# MCU.net
KiCad netlist of a schematic drawn in Altium Designer
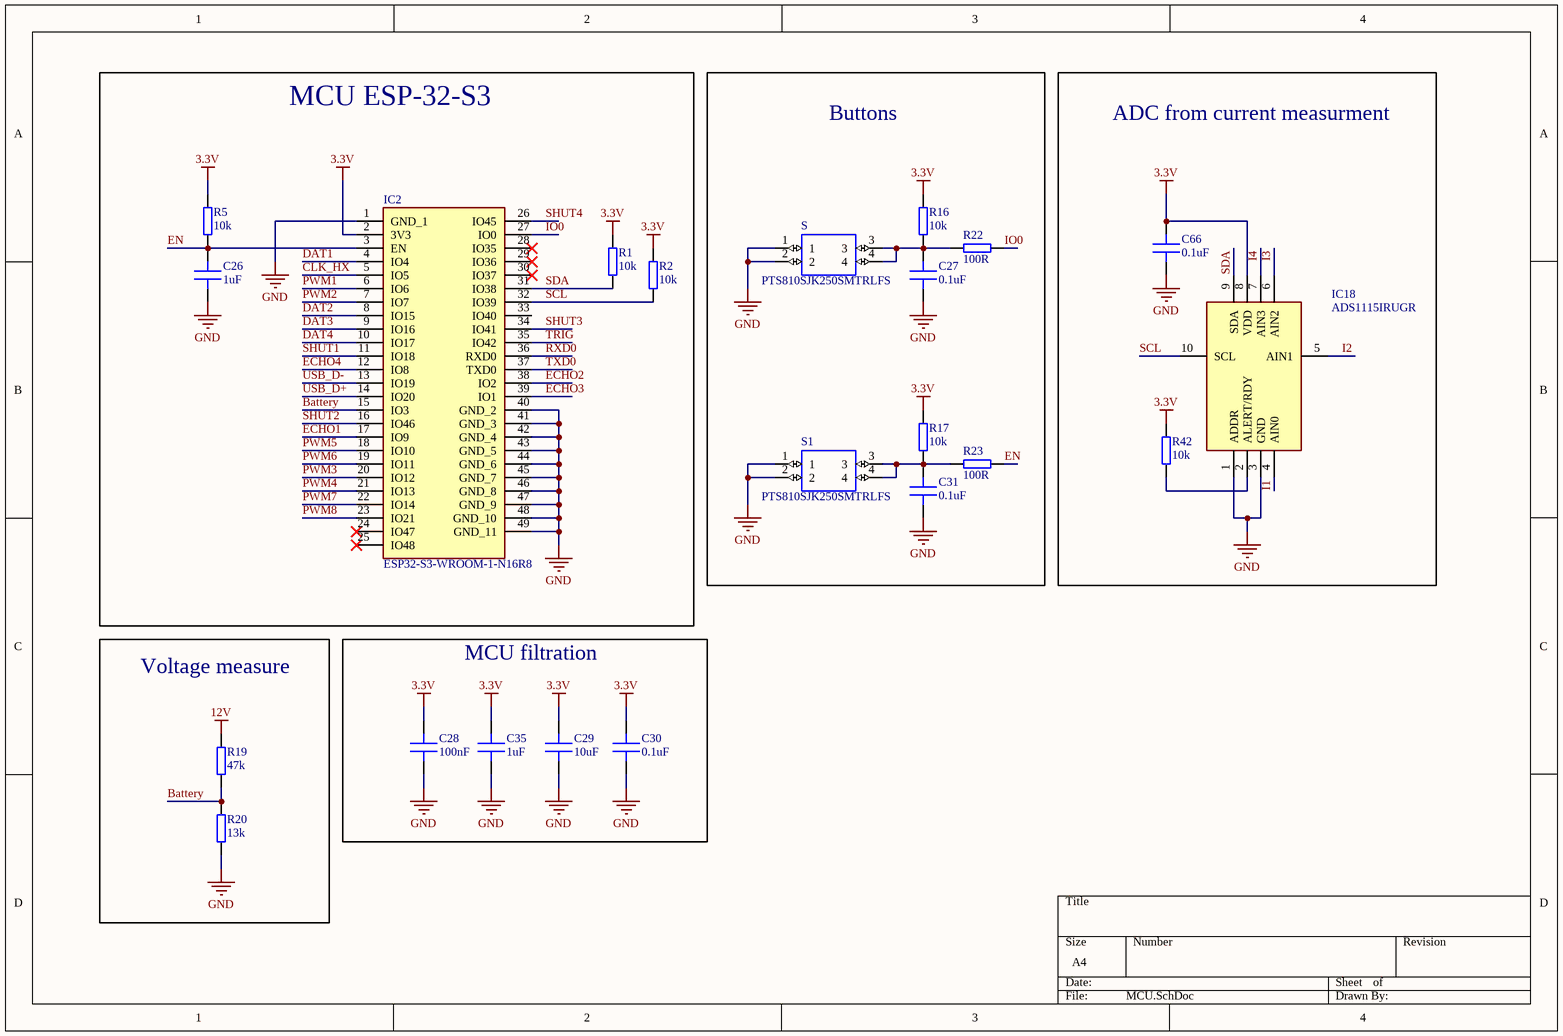
[diagram p0: MCU.SchDoc]

(export (version "E")
  (design (tool "Eeschema 10.0.6"))
  (components
    (comp (ref "C26")
      (value "1uF")
      (footprint "C 0402")
      (description "MLCC Capacitor")
      (libsource (lib "Components") (part "Capacitor"))
    )
    (comp (ref "C27")
      (value "0.1uF")
      (footprint "C 0402")
      (description "MLCC Capacitor")
      (libsource (lib "Components") (part "Capacitor"))
    )
    (comp (ref "C28")
      (value "100nF")
      (footprint "C 0402")
      (description "MLCC Capacitor")
      (libsource (lib "Components") (part "Capacitor"))
    )
    (comp (ref "C29")
      (value "10uF")
      (footprint "C 0402")
      (description "MLCC Capacitor")
      (libsource (lib "Components") (part "Capacitor"))
    )
    (comp (ref "C30")
      (value "0.1uF")
      (footprint "C 0402")
      (description "MLCC Capacitor")
      (libsource (lib "Components") (part "Capacitor"))
    )
    (comp (ref "C31")
      (value "0.1uF")
      (footprint "C 0402")
      (description "MLCC Capacitor")
      (libsource (lib "Components") (part "Capacitor"))
    )
    (comp (ref "C35")
      (value "1uF")
      (footprint "C 0402")
      (description "MLCC Capacitor")
      (libsource (lib "Components") (part "Capacitor"))
    )
    (comp (ref "C66")
      (value "0.1uF")
      (footprint "C 0402")
      (description "MLCC Capacitor")
      (libsource (lib "Components") (part "Capacitor"))
    )
    (comp (ref "IC2")
      (value "ESP32-S3-WROOM-1-N16R8")
      (footprint "SamacSys:ESP32S3WROOM1N16R8")
      (description "Integrated Circuit")
      (fields (field (name "MOUSER PART NUMBER") "356-ESP32S3WRM1N16R8"))
      (libsource (lib "caravan_sch_lib") (part "ESP32-S3-WROOM-1-N16R8"))
    )
    (comp (ref "IC18")
      (value "ADS1115IRUGR")
      (footprint "SamacSys:ADS1115IRUGR")
      (description "Integrated Circuit")
      (fields (field (name "MOUSER PART NUMBER") "595-ADS1115IRUGR"))
      (libsource (lib "caravan_sch_lib") (part "ADS1115IRUGR"))
    )
    (comp (ref "R1")
      (value "10k")
      (footprint "R 0402")
      (description "General pourpouse resistor")
      (libsource (lib "Components") (part "Resistor"))
    )
    (comp (ref "R2")
      (value "10k")
      (footprint "R 0402")
      (description "General pourpouse resistor")
      (libsource (lib "Components") (part "Resistor"))
    )
    (comp (ref "R5")
      (value "10k")
      (footprint "R 0402")
      (description "General pourpouse resistor")
      (libsource (lib "Components") (part "Resistor"))
    )
    (comp (ref "R16")
      (value "10k")
      (footprint "R 0402")
      (description "General pourpouse resistor")
      (libsource (lib "Components") (part "Resistor"))
    )
    (comp (ref "R17")
      (value "10k")
      (footprint "R 0402")
      (description "General pourpouse resistor")
      (libsource (lib "Components") (part "Resistor"))
    )
    (comp (ref "R19")
      (value "47k")
      (footprint "R 0402")
      (description "General pourpouse resistor")
      (libsource (lib "Components") (part "Resistor"))
    )
    (comp (ref "R20")
      (value "13k")
      (footprint "R 0402")
      (description "General pourpouse resistor")
      (libsource (lib "Components") (part "Resistor"))
    )
    (comp (ref "R22")
      (value "100R")
      (footprint "R 0402")
      (description "General pourpouse resistor")
      (libsource (lib "Components") (part "Resistor"))
    )
    (comp (ref "R23")
      (value "100R")
      (footprint "R 0402")
      (description "General pourpouse resistor")
      (libsource (lib "Components") (part "Resistor"))
    )
    (comp (ref "R42")
      (value "10k")
      (footprint "R 0402")
      (description "General pourpouse resistor")
      (libsource (lib "Components") (part "Resistor"))
    )
    (comp (ref "S")
      (value "PTS810SJK250SMTRLFS")
      (footprint "caravan_pcb_lib:PTS810SJG250SMTRLFS")
      (description "Tactile Switch SPST-NO Top Actuated Surface Mount")
      (fields (field (name "MF") "C&K"))
      (libsource (lib "caravan_sch_lib") (part "PTS810SJK250SMTRLFS"))
    )
    (comp (ref "S1")
      (value "PTS810SJK250SMTRLFS")
      (footprint "caravan_pcb_lib:PTS810SJG250SMTRLFS")
      (description "Tactile Switch SPST-NO Top Actuated Surface Mount")
      (fields (field (name "MF") "C&K"))
      (libsource (lib "caravan_sch_lib") (part "PTS810SJK250SMTRLFS"))
    )
  )
  (nets
    (net (code "1") (name "/Battery") (class "Default")
      (node (ref "IC2") (pin "15") (pinfunction "IO3_15") (pintype "passive"))
      (node (ref "R19") (pin "1") (pinfunction "1_1") (pintype "passive"))
      (node (ref "R20") (pin "2") (pinfunction "2_2") (pintype "passive"))
    )
    (net (code "2") (name "/CLK_HX") (class "Default")
      (node (ref "IC2") (pin "5") (pinfunction "IO5_5") (pintype "passive"))
    )
    (net (code "3") (name "/DAT1") (class "Default")
      (node (ref "IC2") (pin "4") (pinfunction "IO4_4") (pintype "passive"))
    )
    (net (code "4") (name "/DAT2") (class "Default")
      (node (ref "IC2") (pin "8") (pinfunction "IO15_8") (pintype "passive"))
    )
    (net (code "5") (name "/DAT3") (class "Default")
      (node (ref "IC2") (pin "9") (pinfunction "IO16_9") (pintype "passive"))
    )
    (net (code "6") (name "/DAT4") (class "Default")
      (node (ref "IC2") (pin "10") (pinfunction "IO17_10") (pintype "passive"))
    )
    (net (code "7") (name "/ECHO1") (class "Default")
      (node (ref "IC2") (pin "17") (pinfunction "IO9_17") (pintype "passive"))
    )
    (net (code "8") (name "/ECHO2") (class "Default")
      (node (ref "IC2") (pin "38") (pinfunction "IO2_38") (pintype "passive"))
    )
    (net (code "9") (name "/ECHO3") (class "Default")
      (node (ref "IC2") (pin "39") (pinfunction "IO1_39") (pintype "passive"))
    )
    (net (code "10") (name "/ECHO4") (class "Default")
      (node (ref "IC2") (pin "12") (pinfunction "IO8_12") (pintype "passive"))
    )
    (net (code "11") (name "/EN") (class "Default")
      (node (ref "C26") (pin "1") (pinfunction "1_1") (pintype "passive"))
      (node (ref "IC2") (pin "3") (pinfunction "EN_3") (pintype "passive"))
      (node (ref "R23") (pin "1") (pinfunction "1_1") (pintype "passive"))
      (node (ref "R5") (pin "1") (pinfunction "1_1") (pintype "passive"))
    )
    (net (code "12") (name "/I1") (class "Default")
      (node (ref "IC18") (pin "4") (pinfunction "AIN0_4") (pintype "passive"))
    )
    (net (code "13") (name "/I2") (class "Default")
      (node (ref "IC18") (pin "5") (pinfunction "AIN1_5") (pintype "passive"))
    )
    (net (code "14") (name "/I3") (class "Default")
      (node (ref "IC18") (pin "6") (pinfunction "AIN2_6") (pintype "passive"))
    )
    (net (code "15") (name "/I4") (class "Default")
      (node (ref "IC18") (pin "7") (pinfunction "AIN3_7") (pintype "passive"))
    )
    (net (code "16") (name "/IO0") (class "Default")
      (node (ref "IC2") (pin "27") (pinfunction "IO0_27") (pintype "passive"))
      (node (ref "R22") (pin "1") (pinfunction "1_1") (pintype "passive"))
    )
    (net (code "17") (name "/PWM1") (class "Default")
      (node (ref "IC2") (pin "6") (pinfunction "IO6_6") (pintype "passive"))
    )
    (net (code "18") (name "/PWM2") (class "Default")
      (node (ref "IC2") (pin "7") (pinfunction "IO7_7") (pintype "passive"))
    )
    (net (code "19") (name "/PWM3") (class "Default")
      (node (ref "IC2") (pin "20") (pinfunction "IO12_20") (pintype "passive"))
    )
    (net (code "20") (name "/PWM4") (class "Default")
      (node (ref "IC2") (pin "21") (pinfunction "IO13_21") (pintype "passive"))
    )
    (net (code "21") (name "/PWM5") (class "Default")
      (node (ref "IC2") (pin "18") (pinfunction "IO10_18") (pintype "passive"))
    )
    (net (code "22") (name "/PWM6") (class "Default")
      (node (ref "IC2") (pin "19") (pinfunction "IO11_19") (pintype "passive"))
    )
    (net (code "23") (name "/PWM7") (class "Default")
      (node (ref "IC2") (pin "22") (pinfunction "IO14_22") (pintype "passive"))
    )
    (net (code "24") (name "/PWM8") (class "Default")
      (node (ref "IC2") (pin "23") (pinfunction "IO21_23") (pintype "passive"))
    )
    (net (code "25") (name "/RXD0") (class "Default")
      (node (ref "IC2") (pin "36") (pinfunction "RXD0_36") (pintype "passive"))
    )
    (net (code "26") (name "/SCL") (class "Default")
      (node (ref "IC18") (pin "10") (pinfunction "SCL_10") (pintype "passive"))
      (node (ref "IC2") (pin "32") (pinfunction "IO39_32") (pintype "passive"))
      (node (ref "R2") (pin "1") (pinfunction "1_1") (pintype "passive"))
    )
    (net (code "27") (name "/SDA") (class "Default")
      (node (ref "IC18") (pin "9") (pinfunction "SDA_9") (pintype "passive"))
      (node (ref "IC2") (pin "31") (pinfunction "IO38_31") (pintype "passive"))
      (node (ref "R1") (pin "1") (pinfunction "1_1") (pintype "passive"))
    )
    (net (code "28") (name "/SHUT1") (class "Default")
      (node (ref "IC2") (pin "11") (pinfunction "IO18_11") (pintype "passive"))
    )
    (net (code "29") (name "/SHUT2") (class "Default")
      (node (ref "IC2") (pin "16") (pinfunction "IO46_16") (pintype "passive"))
    )
    (net (code "30") (name "/SHUT3") (class "Default")
      (node (ref "IC2") (pin "34") (pinfunction "IO41_34") (pintype "passive"))
    )
    (net (code "31") (name "/SHUT4") (class "Default")
      (node (ref "IC2") (pin "26") (pinfunction "IO45_26") (pintype "passive"))
    )
    (net (code "32") (name "/TRIG") (class "Default")
      (node (ref "IC2") (pin "35") (pinfunction "IO42_35") (pintype "passive"))
    )
    (net (code "33") (name "/TXD0") (class "Default")
      (node (ref "IC2") (pin "37") (pinfunction "TXD0_37") (pintype "passive"))
    )
    (net (code "34") (name "/USB_D+") (class "Default")
      (node (ref "IC2") (pin "14") (pinfunction "IO20_14") (pintype "passive"))
    )
    (net (code "35") (name "/USB_D-") (class "Default")
      (node (ref "IC2") (pin "13") (pinfunction "IO19_13") (pintype "passive"))
    )
    (net (code "36") (name "3.3V") (class "Default")
      (node (ref "C28") (pin "1") (pinfunction "1_1") (pintype "passive"))
      (node (ref "C29") (pin "1") (pinfunction "1_1") (pintype "passive"))
      (node (ref "C30") (pin "1") (pinfunction "1_1") (pintype "passive"))
      (node (ref "C35") (pin "1") (pinfunction "1_1") (pintype "passive"))
      (node (ref "C66") (pin "1") (pinfunction "1_1") (pintype "passive"))
      (node (ref "IC18") (pin "8") (pinfunction "VDD_8") (pintype "passive"))
      (node (ref "IC2") (pin "2") (pinfunction "3V3_2") (pintype "passive"))
      (node (ref "R1") (pin "2") (pinfunction "2_2") (pintype "passive"))
      (node (ref "R16") (pin "2") (pinfunction "2_2") (pintype "passive"))
      (node (ref "R17") (pin "2") (pinfunction "2_2") (pintype "passive"))
      (node (ref "R2") (pin "2") (pinfunction "2_2") (pintype "passive"))
      (node (ref "R42") (pin "2") (pinfunction "2_2") (pintype "passive"))
      (node (ref "R5") (pin "2") (pinfunction "2_2") (pintype "passive"))
    )
    (net (code "37") (name "12V") (class "Default")
      (node (ref "R19") (pin "2") (pinfunction "2_2") (pintype "passive"))
    )
    (net (code "38") (name "GND") (class "Default")
      (node (ref "C26") (pin "2") (pinfunction "2_2") (pintype "passive"))
      (node (ref "C27") (pin "2") (pinfunction "2_2") (pintype "passive"))
      (node (ref "C28") (pin "2") (pinfunction "2_2") (pintype "passive"))
      (node (ref "C29") (pin "2") (pinfunction "2_2") (pintype "passive"))
      (node (ref "C30") (pin "2") (pinfunction "2_2") (pintype "passive"))
      (node (ref "C31") (pin "2") (pinfunction "2_2") (pintype "passive"))
      (node (ref "C35") (pin "2") (pinfunction "2_2") (pintype "passive"))
      (node (ref "C66") (pin "2") (pinfunction "2_2") (pintype "passive"))
      (node (ref "IC18") (pin "1") (pinfunction "ADDR_1") (pintype "passive"))
      (node (ref "IC18") (pin "3") (pinfunction "GND_3") (pintype "passive"))
      (node (ref "IC2") (pin "1") (pinfunction "GND_1_1") (pintype "passive"))
      (node (ref "IC2") (pin "40") (pinfunction "GND_2_40") (pintype "passive"))
      (node (ref "IC2") (pin "41") (pinfunction "GND_3_41") (pintype "passive"))
      (node (ref "IC2") (pin "42") (pinfunction "GND_4_42") (pintype "passive"))
      (node (ref "IC2") (pin "43") (pinfunction "GND_5_43") (pintype "passive"))
      (node (ref "IC2") (pin "44") (pinfunction "GND_6_44") (pintype "passive"))
      (node (ref "IC2") (pin "45") (pinfunction "GND_7_45") (pintype "passive"))
      (node (ref "IC2") (pin "46") (pinfunction "GND_8_46") (pintype "passive"))
      (node (ref "IC2") (pin "47") (pinfunction "GND_9_47") (pintype "passive"))
      (node (ref "IC2") (pin "48") (pinfunction "GND_10_48") (pintype "passive"))
      (node (ref "IC2") (pin "49") (pinfunction "GND_11_49") (pintype "passive"))
      (node (ref "R20") (pin "1") (pinfunction "1_1") (pintype "passive"))
      (node (ref "S") (pin "1") (pinfunction "1_1") (pintype "bidirectional"))
      (node (ref "S") (pin "2") (pinfunction "2_2") (pintype "bidirectional"))
      (node (ref "S1") (pin "1") (pinfunction "1_1") (pintype "bidirectional"))
      (node (ref "S1") (pin "2") (pinfunction "2_2") (pintype "bidirectional"))
    )
    (net (code "39") (name "Net-(C27-Pad1)") (class "Default")
      (node (ref "C27") (pin "1") (pinfunction "1_1") (pintype "passive"))
      (node (ref "R16") (pin "1") (pinfunction "1_1") (pintype "passive"))
      (node (ref "R22") (pin "2") (pinfunction "2_2") (pintype "passive"))
      (node (ref "S") (pin "3") (pinfunction "3_3") (pintype "bidirectional"))
      (node (ref "S") (pin "4") (pinfunction "4_4") (pintype "bidirectional"))
    )
    (net (code "40") (name "Net-(C31-Pad1)") (class "Default")
      (node (ref "C31") (pin "1") (pinfunction "1_1") (pintype "passive"))
      (node (ref "R17") (pin "1") (pinfunction "1_1") (pintype "passive"))
      (node (ref "R23") (pin "2") (pinfunction "2_2") (pintype "passive"))
      (node (ref "S1") (pin "3") (pinfunction "3_3") (pintype "bidirectional"))
      (node (ref "S1") (pin "4") (pinfunction "4_4") (pintype "bidirectional"))
    )
    (net (code "41") (name "Net-(IC18-ALERT{slash}RDY)") (class "Default")
      (node (ref "IC18") (pin "2") (pinfunction "ALERT/RDY_2") (pintype "passive"))
      (node (ref "R42") (pin "1") (pinfunction "1_1") (pintype "passive"))
    )
    (net (code "42") (name "unconnected-(IC2-IO35-Pad28)") (class "Default")
      (node (ref "IC2") (pin "28") (pinfunction "IO35_28") (pintype "passive+no_connect"))
    )
    (net (code "43") (name "unconnected-(IC2-IO36-Pad29)") (class "Default")
      (node (ref "IC2") (pin "29") (pinfunction "IO36_29") (pintype "passive+no_connect"))
    )
    (net (code "44") (name "unconnected-(IC2-IO37-Pad30)") (class "Default")
      (node (ref "IC2") (pin "30") (pinfunction "IO37_30") (pintype "passive+no_connect"))
    )
    (net (code "45") (name "unconnected-(IC2-IO40-Pad33)") (class "Default")
      (node (ref "IC2") (pin "33") (pinfunction "IO40_33") (pintype "passive"))
    )
    (net (code "46") (name "unconnected-(IC2-IO47-Pad24)") (class "Default")
      (node (ref "IC2") (pin "24") (pinfunction "IO47_24") (pintype "passive+no_connect"))
    )
    (net (code "47") (name "unconnected-(IC2-IO48-Pad25)") (class "Default")
      (node (ref "IC2") (pin "25") (pinfunction "IO48_25") (pintype "passive+no_connect"))
    )
  )
)
